# ECE411-Group6-V5.net
KiCad netlist of a schematic drawn in EAGLE
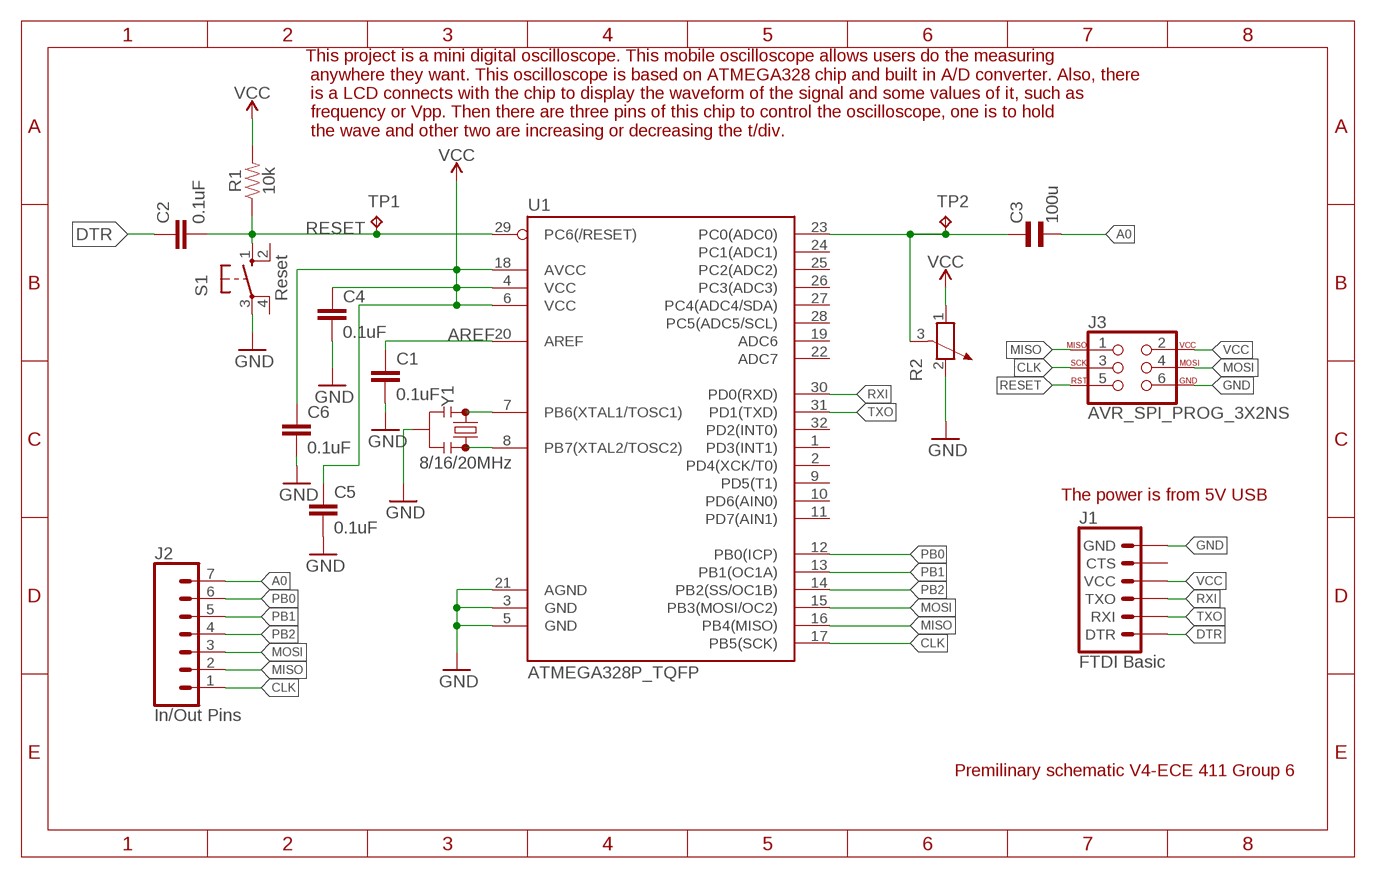
[diagram p0: schematic, sheet 1]

(export (version "E")
  (design (tool "Eeschema 10.0.6"))
  (components
    (comp (ref "C1")
      (value "0.1uF")
      (footprint "eagle-import:0603")
      (libsource (lib "eagle-import") (part "0.1UF-0603-25V-5%"))
    )
    (comp (ref "C2")
      (value "0.1uF")
      (footprint "eagle-import:0603")
      (libsource (lib "eagle-import") (part "0.1UF-0603-25V-5%"))
    )
    (comp (ref "C3")
      (value "100u")
      (footprint "eagle-import:EU25-10")
      (libsource (lib "eagle-import") (part "EL-BI25-10AXIAL"))
    )
    (comp (ref "C4")
      (value "0.1uF")
      (footprint "eagle-import:0603")
      (libsource (lib "eagle-import") (part "0.1UF-0603-25V-5%"))
    )
    (comp (ref "C5")
      (value "0.1uF")
      (footprint "eagle-import:0603")
      (libsource (lib "eagle-import") (part "0.1UF-0603-25V-5%"))
    )
    (comp (ref "C6")
      (value "0.1uF")
      (footprint "eagle-import:0603")
      (libsource (lib "eagle-import") (part "0.1UF-0603-25V-5%"))
    )
    (comp (ref "J1")
      (value "FTDI Basic")
      (footprint "eagle-import:1X06")
      (libsource (lib "eagle-import") (part "6_PIN_SERIAL_TARGET"))
    )
    (comp (ref "J2")
      (value "In/Out Pins")
      (footprint "eagle-import:1X07")
      (libsource (lib "eagle-import") (part "CONN_07"))
    )
    (comp (ref "J3")
      (value "AVR_SPI_PROG_3X2NS")
      (footprint "eagle-import:2X3-NS")
      (libsource (lib "eagle-import") (part "AVR_SPI_PROG_3X2NS"))
    )
    (comp (ref "R1")
      (value "10k")
      (footprint "eagle-import:0603")
      (libsource (lib "eagle-import") (part "10KOHM-0603-1/10W-1%"))
    )
    (comp (ref "R2")
      (value "POTENTIOMETER_PT-10")
      (footprint "eagle-import:PT-10")
      (libsource (lib "eagle-import") (part "POTENTIOMETER_PT-10"))
    )
    (comp (ref "S1")
      (value "Reset")
      (footprint "eagle-import:B3F-10XX")
      (fields (field (name "MPN") "B3F-1000"))
      (libsource (lib "eagle-import") (part "10-XX"))
    )
    (comp (ref "TP1")
      (value "TPB1,27")
      (footprint "eagle-import:B1,27")
      (libsource (lib "eagle-import") (part "TPB1,27"))
    )
    (comp (ref "TP2")
      (value "TPB1,27")
      (footprint "eagle-import:B1,27")
      (libsource (lib "eagle-import") (part "TPB1,27"))
    )
    (comp (ref "U1")
      (value "ATMEGA328P_TQFP")
      (footprint "eagle-import:TQFP32-08")
      (libsource (lib "eagle-import") (part "ATMEGA328P_TQFP"))
    )
    (comp (ref "Y1")
      (value "8/16/20MHz")
      (footprint "eagle-import:RESONATOR-SMD-3.2X1.3")
      (libsource (lib "eagle-import") (part "RESONATORSMD-3.2X1.3"))
    )
  )
  (nets
    (net (code "1") (name "/AREF") (class "Default")
      (node (ref "C1") (pin "1") (pinfunction "1_1") (pintype "passive"))
      (node (ref "U1") (pin "20") (pinfunction "AREF_20") (pintype "bidirectional"))
    )
    (net (code "2") (name "A0") (class "Default")
      (node (ref "C3") (pin "2") (pinfunction "2_2") (pintype "passive"))
      (node (ref "J2") (pin "7") (pinfunction "7_7") (pintype "passive"))
    )
    (net (code "3") (name "CLK") (class "Default")
      (node (ref "J2") (pin "1") (pinfunction "1_1") (pintype "passive"))
      (node (ref "J3") (pin "3") (pinfunction "3_3") (pintype "passive"))
      (node (ref "U1") (pin "17") (pinfunction "PB5(SCK)_17") (pintype "bidirectional"))
    )
    (net (code "4") (name "DTR") (class "Default")
      (node (ref "C2") (pin "1") (pinfunction "1_1") (pintype "passive"))
      (node (ref "J1") (pin "1") (pinfunction "DTR_1") (pintype "passive"))
    )
    (net (code "5") (name "GND") (class "Default")
      (node (ref "C1") (pin "2") (pinfunction "2_2") (pintype "passive"))
      (node (ref "C4") (pin "2") (pinfunction "2_2") (pintype "passive"))
      (node (ref "C5") (pin "2") (pinfunction "2_2") (pintype "passive"))
      (node (ref "C6") (pin "2") (pinfunction "2_2") (pintype "passive"))
      (node (ref "J1") (pin "6") (pinfunction "GND_6") (pintype "passive"))
      (node (ref "J3") (pin "6") (pinfunction "6_6") (pintype "passive"))
      (node (ref "R2") (pin "2") (pinfunction "2_2") (pintype "passive"))
      (node (ref "S1") (pin "3") (pinfunction "P_3") (pintype "passive"))
      (node (ref "U1") (pin "21") (pinfunction "AGND_21") (pintype "bidirectional"))
      (node (ref "U1") (pin "3") (pinfunction "GND_3") (pintype "bidirectional"))
      (node (ref "U1") (pin "5") (pinfunction "GND_5") (pintype "bidirectional"))
      (node (ref "Y1") (pin "2") (pinfunction "2_2") (pintype "passive"))
    )
    (net (code "6") (name "MISO") (class "Default")
      (node (ref "J2") (pin "2") (pinfunction "2_2") (pintype "passive"))
      (node (ref "J3") (pin "1") (pinfunction "1_1") (pintype "passive"))
      (node (ref "U1") (pin "16") (pinfunction "PB4(MISO)_16") (pintype "bidirectional"))
    )
    (net (code "7") (name "MOSI") (class "Default")
      (node (ref "J2") (pin "3") (pinfunction "3_3") (pintype "passive"))
      (node (ref "J3") (pin "4") (pinfunction "4_4") (pintype "passive"))
      (node (ref "U1") (pin "15") (pinfunction "PB3(MOSI/OC2)_15") (pintype "bidirectional"))
    )
    (net (code "8") (name "Net-(U1-PB6(XTAL1{slash}TOSC1))") (class "Default")
      (node (ref "U1") (pin "7") (pinfunction "PB6(XTAL1/TOSC1)_7") (pintype "bidirectional"))
      (node (ref "Y1") (pin "1") (pinfunction "1_1") (pintype "passive"))
    )
    (net (code "9") (name "Net-(U1-PB7(XTAL2{slash}TOSC2))") (class "Default")
      (node (ref "U1") (pin "8") (pinfunction "PB7(XTAL2/TOSC2)_8") (pintype "bidirectional"))
      (node (ref "Y1") (pin "3") (pinfunction "3_3") (pintype "passive"))
    )
    (net (code "10") (name "Net-(U1-PC0(ADC0))") (class "Default")
      (node (ref "C3") (pin "1") (pinfunction "1_1") (pintype "passive"))
      (node (ref "R2") (pin "3") (pinfunction "3_3") (pintype "passive"))
      (node (ref "TP2") (pin "TP") (pinfunction "TP_TP") (pintype "input"))
      (node (ref "U1") (pin "23") (pinfunction "PC0(ADC0)_23") (pintype "bidirectional"))
    )
    (net (code "11") (name "PB0") (class "Default")
      (node (ref "J2") (pin "6") (pinfunction "6_6") (pintype "passive"))
      (node (ref "U1") (pin "12") (pinfunction "PB0(ICP)_12") (pintype "bidirectional"))
    )
    (net (code "12") (name "PB1") (class "Default")
      (node (ref "J2") (pin "5") (pinfunction "5_5") (pintype "passive"))
      (node (ref "U1") (pin "13") (pinfunction "PB1(OC1A)_13") (pintype "bidirectional"))
    )
    (net (code "13") (name "PB2") (class "Default")
      (node (ref "J2") (pin "4") (pinfunction "4_4") (pintype "passive"))
      (node (ref "U1") (pin "14") (pinfunction "PB2(SS/OC1B)_14") (pintype "bidirectional"))
    )
    (net (code "14") (name "RESET") (class "Default")
      (node (ref "C2") (pin "2") (pinfunction "2_2") (pintype "passive"))
      (node (ref "J3") (pin "5") (pinfunction "5_5") (pintype "passive"))
      (node (ref "R1") (pin "1") (pinfunction "1_1") (pintype "passive"))
      (node (ref "S1") (pin "1") (pinfunction "S_1") (pintype "passive"))
      (node (ref "TP1") (pin "TP") (pinfunction "TP_TP") (pintype "input"))
      (node (ref "U1") (pin "29") (pinfunction "PC6(/RESET)_29") (pintype "bidirectional"))
    )
    (net (code "15") (name "RXI") (class "Default")
      (node (ref "J1") (pin "3") (pinfunction "TXO_3") (pintype "passive"))
      (node (ref "U1") (pin "30") (pinfunction "PD0(RXD)_30") (pintype "bidirectional"))
    )
    (net (code "16") (name "TXO") (class "Default")
      (node (ref "J1") (pin "2") (pinfunction "RXI_2") (pintype "passive"))
      (node (ref "U1") (pin "31") (pinfunction "PD1(TXD)_31") (pintype "bidirectional"))
    )
    (net (code "17") (name "VCC") (class "Default")
      (node (ref "C4") (pin "1") (pinfunction "1_1") (pintype "passive"))
      (node (ref "C5") (pin "1") (pinfunction "1_1") (pintype "passive"))
      (node (ref "C6") (pin "1") (pinfunction "1_1") (pintype "passive"))
      (node (ref "J1") (pin "4") (pinfunction "VCC_4") (pintype "passive"))
      (node (ref "J3") (pin "2") (pinfunction "2_2") (pintype "passive"))
      (node (ref "R1") (pin "2") (pinfunction "2_2") (pintype "passive"))
      (node (ref "R2") (pin "1") (pinfunction "1_1") (pintype "passive"))
      (node (ref "U1") (pin "18") (pinfunction "AVCC_18") (pintype "bidirectional"))
      (node (ref "U1") (pin "4") (pinfunction "VCC_4") (pintype "bidirectional"))
      (node (ref "U1") (pin "6") (pinfunction "VCC_6") (pintype "bidirectional"))
    )
    (net (code "18") (name "unconnected-(J1-CTS-Pad5)") (class "Default")
      (node (ref "J1") (pin "5") (pinfunction "CTS_5") (pintype "passive"))
    )
    (net (code "19") (name "unconnected-(S1-P1-Pad4)") (class "Default")
      (node (ref "S1") (pin "4") (pinfunction "P1_4") (pintype "passive"))
    )
    (net (code "20") (name "unconnected-(S1-S1-Pad2)") (class "Default")
      (node (ref "S1") (pin "2") (pinfunction "S1_2") (pintype "passive"))
    )
    (net (code "21") (name "unconnected-(U1-ADC6-Pad19)") (class "Default")
      (node (ref "U1") (pin "19") (pinfunction "ADC6_19") (pintype "bidirectional"))
    )
    (net (code "22") (name "unconnected-(U1-ADC7-Pad22)") (class "Default")
      (node (ref "U1") (pin "22") (pinfunction "ADC7_22") (pintype "bidirectional"))
    )
    (net (code "23") (name "unconnected-(U1-PC1(ADC1)-Pad24)") (class "Default")
      (node (ref "U1") (pin "24") (pinfunction "PC1(ADC1)_24") (pintype "bidirectional"))
    )
    (net (code "24") (name "unconnected-(U1-PC2(ADC2)-Pad25)") (class "Default")
      (node (ref "U1") (pin "25") (pinfunction "PC2(ADC2)_25") (pintype "bidirectional"))
    )
    (net (code "25") (name "unconnected-(U1-PC3(ADC3)-Pad26)") (class "Default")
      (node (ref "U1") (pin "26") (pinfunction "PC3(ADC3)_26") (pintype "bidirectional"))
    )
    (net (code "26") (name "unconnected-(U1-PC4(ADC4{slash}SDA)-Pad27)") (class "Default")
      (node (ref "U1") (pin "27") (pinfunction "PC4(ADC4/SDA)_27") (pintype "bidirectional"))
    )
    (net (code "27") (name "unconnected-(U1-PC5(ADC5{slash}SCL)-Pad28)") (class "Default")
      (node (ref "U1") (pin "28") (pinfunction "PC5(ADC5/SCL)_28") (pintype "bidirectional"))
    )
    (net (code "28") (name "unconnected-(U1-PD2(INT0)-Pad32)") (class "Default")
      (node (ref "U1") (pin "32") (pinfunction "PD2(INT0)_32") (pintype "bidirectional"))
    )
    (net (code "29") (name "unconnected-(U1-PD3(INT1)-Pad1)") (class "Default")
      (node (ref "U1") (pin "1") (pinfunction "PD3(INT1)_1") (pintype "bidirectional"))
    )
    (net (code "30") (name "unconnected-(U1-PD4(XCK{slash}T0)-Pad2)") (class "Default")
      (node (ref "U1") (pin "2") (pinfunction "PD4(XCK/T0)_2") (pintype "bidirectional"))
    )
    (net (code "31") (name "unconnected-(U1-PD5(T1)-Pad9)") (class "Default")
      (node (ref "U1") (pin "9") (pinfunction "PD5(T1)_9") (pintype "bidirectional"))
    )
    (net (code "32") (name "unconnected-(U1-PD6(AIN0)-Pad10)") (class "Default")
      (node (ref "U1") (pin "10") (pinfunction "PD6(AIN0)_10") (pintype "bidirectional"))
    )
    (net (code "33") (name "unconnected-(U1-PD7(AIN1)-Pad11)") (class "Default")
      (node (ref "U1") (pin "11") (pinfunction "PD7(AIN1)_11") (pintype "bidirectional"))
    )
  )
)
